# TPSPowerSupply.net
KiCad netlist of a schematic drawn in EAGLE
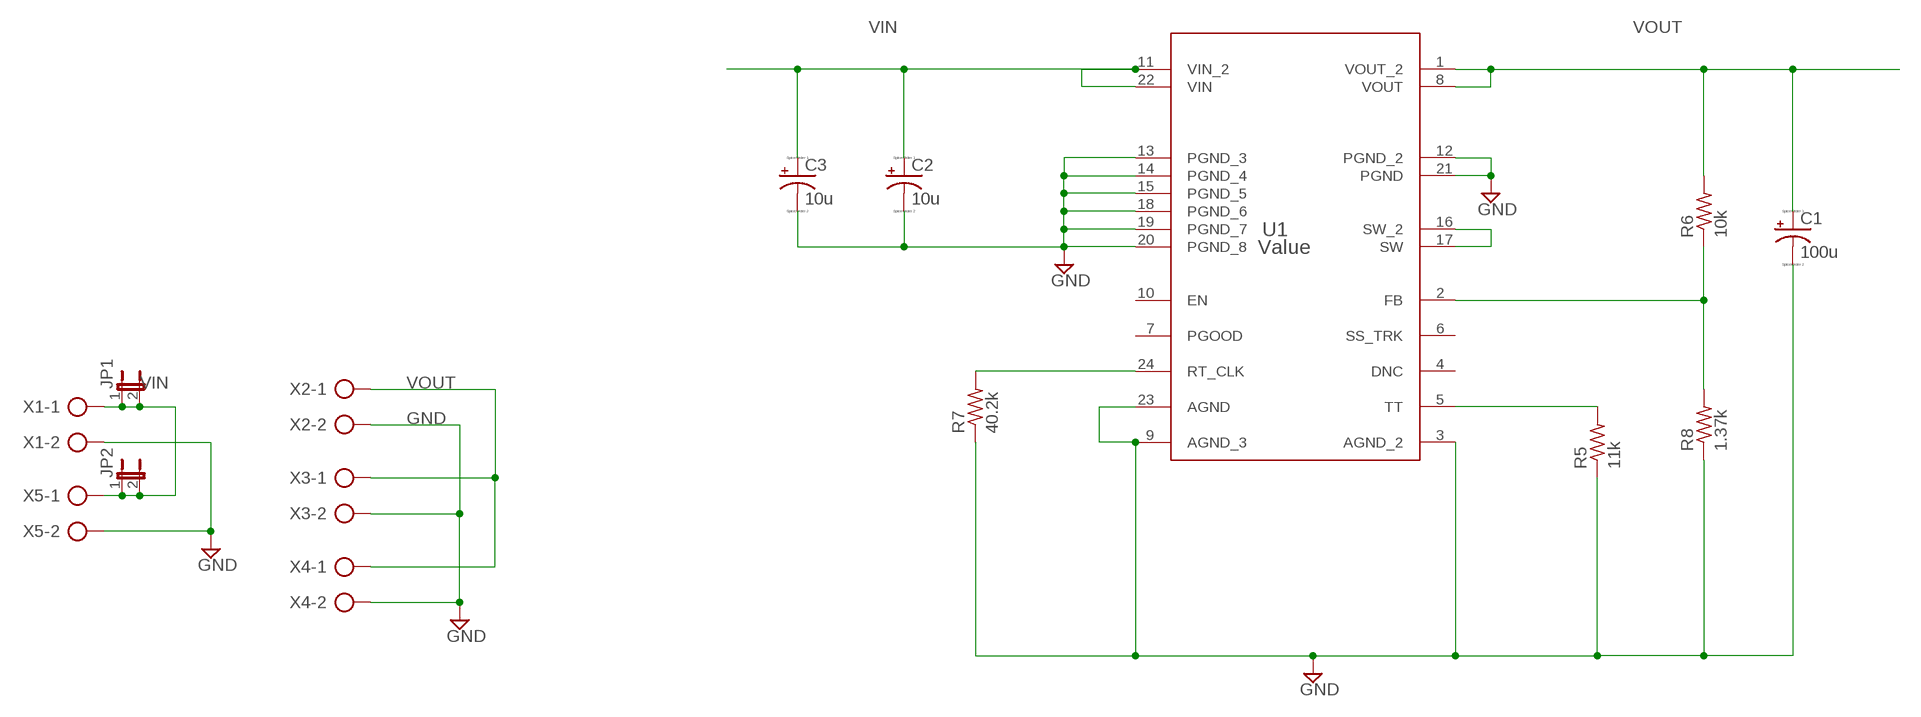
[diagram p0: schematic, sheet 1]

(export (version "E")
  (design (tool "Eeschema 10.0.6"))
  (components
    (comp (ref "C1")
      (value "100u")
      (footprint "eagle-import:TT5D11L")
      (libsource (lib "eagle-import") (part "CPOL-USTT5D11L"))
    )
    (comp (ref "C2")
      (value "10u")
      (footprint "eagle-import:TT5D11L")
      (libsource (lib "eagle-import") (part "CPOL-USTT5D11L"))
    )
    (comp (ref "C3")
      (value "10u")
      (footprint "eagle-import:TT5D11L")
      (libsource (lib "eagle-import") (part "CPOL-USTT5D11L"))
    )
    (comp (ref "JP1")
      (value "JP1E")
      (footprint "eagle-import:JP1")
      (libsource (lib "eagle-import") (part "JP1E"))
    )
    (comp (ref "JP2")
      (value "JP1E")
      (footprint "eagle-import:JP1")
      (libsource (lib "eagle-import") (part "JP1E"))
    )
    (comp (ref "R5")
      (value "11k")
      (footprint "eagle-import:0411_15")
      (libsource (lib "eagle-import") (part "R-US_0411/15"))
    )
    (comp (ref "R6")
      (value "10k")
      (footprint "eagle-import:0411_15")
      (libsource (lib "eagle-import") (part "R-US_0411/15"))
    )
    (comp (ref "R7")
      (value "40.2k")
      (footprint "eagle-import:0411_15")
      (libsource (lib "eagle-import") (part "R-US_0411/15"))
    )
    (comp (ref "R8")
      (value "1.37k")
      (footprint "eagle-import:0411_15")
      (libsource (lib "eagle-import") (part "R-US_0411/15"))
    )
    (comp (ref "U1")
      (value "Value")
      (footprint "eagle-import:MOL0024A")
      (fields
        (field (name "MANUFACTURER") "Texas Instruments")
        (field (name "MANUFACTURER_PART_NUMBER") "TPSM84824MOLR")
      )
      (libsource (lib "eagle-import") (part "TPSM84824MOLR"))
    )
    (comp (ref "X1")
      (value "AK500/2")
      (footprint "eagle-import:AK500_2")
      (libsource (lib "eagle-import") (part "AK500/2"))
    )
    (comp (ref "X2")
      (value "AK500/2")
      (footprint "eagle-import:AK500_2")
      (libsource (lib "eagle-import") (part "AK500/2"))
    )
    (comp (ref "X3")
      (value "AK500/2")
      (footprint "eagle-import:AK500_2")
      (libsource (lib "eagle-import") (part "AK500/2"))
    )
    (comp (ref "X4")
      (value "AK500/2")
      (footprint "eagle-import:AK500_2")
      (libsource (lib "eagle-import") (part "AK500/2"))
    )
    (comp (ref "X5")
      (value "AK500/2")
      (footprint "eagle-import:AK500_2")
      (libsource (lib "eagle-import") (part "AK500/2"))
    )
  )
  (nets
    (net (code "1") (name "/VIN") (class "Default")
      (node (ref "C2") (pin "+") (pinfunction "+_+") (pintype "passive"))
      (node (ref "C3") (pin "+") (pinfunction "+_+") (pintype "passive"))
      (node (ref "JP1") (pin "1") (pinfunction "1_1") (pintype "passive"))
      (node (ref "JP1") (pin "2") (pinfunction "2_2") (pintype "passive"))
      (node (ref "JP2") (pin "1") (pinfunction "1_1") (pintype "passive"))
      (node (ref "JP2") (pin "2") (pinfunction "2_2") (pintype "passive"))
      (node (ref "U1") (pin "11") (pinfunction "VIN_2_11") (pintype "power_in"))
      (node (ref "U1") (pin "22") (pinfunction "VIN_22") (pintype "power_in"))
      (node (ref "X1") (pin "1") (pinfunction "KL_1") (pintype "passive"))
      (node (ref "X5") (pin "1") (pinfunction "KL_1") (pintype "passive"))
    )
    (net (code "2") (name "/VOUT") (class "Default")
      (node (ref "C1") (pin "+") (pinfunction "+_+") (pintype "passive"))
      (node (ref "R6") (pin "2") (pinfunction "2_2") (pintype "passive"))
      (node (ref "U1") (pin "1") (pinfunction "VOUT_2_1") (pintype "power_in"))
      (node (ref "U1") (pin "8") (pinfunction "VOUT_8") (pintype "power_in"))
      (node (ref "X2") (pin "1") (pinfunction "KL_1") (pintype "passive"))
      (node (ref "X3") (pin "1") (pinfunction "KL_1") (pintype "passive"))
      (node (ref "X4") (pin "1") (pinfunction "KL_1") (pintype "passive"))
    )
    (net (code "3") (name "GND") (class "Default")
      (node (ref "C1") (pin "-") (pinfunction "-_-") (pintype "passive"))
      (node (ref "C2") (pin "-") (pinfunction "-_-") (pintype "passive"))
      (node (ref "C3") (pin "-") (pinfunction "-_-") (pintype "passive"))
      (node (ref "R5") (pin "1") (pinfunction "1_1") (pintype "passive"))
      (node (ref "R7") (pin "1") (pinfunction "1_1") (pintype "passive"))
      (node (ref "R8") (pin "1") (pinfunction "1_1") (pintype "passive"))
      (node (ref "U1") (pin "12") (pinfunction "PGND_2_12") (pintype "power_in"))
      (node (ref "U1") (pin "13") (pinfunction "PGND_3_13") (pintype "power_in"))
      (node (ref "U1") (pin "14") (pinfunction "PGND_4_14") (pintype "power_in"))
      (node (ref "U1") (pin "15") (pinfunction "PGND_5_15") (pintype "power_in"))
      (node (ref "U1") (pin "18") (pinfunction "PGND_6_18") (pintype "power_in"))
      (node (ref "U1") (pin "19") (pinfunction "PGND_7_19") (pintype "power_in"))
      (node (ref "U1") (pin "20") (pinfunction "PGND_8_20") (pintype "power_in"))
      (node (ref "U1") (pin "21") (pinfunction "PGND_21") (pintype "power_in"))
      (node (ref "U1") (pin "23") (pinfunction "AGND_23") (pintype "power_in"))
      (node (ref "U1") (pin "3") (pinfunction "AGND_2_3") (pintype "power_in"))
      (node (ref "U1") (pin "9") (pinfunction "AGND_3_9") (pintype "power_in"))
      (node (ref "X1") (pin "2") (pinfunction "KL_2") (pintype "passive"))
      (node (ref "X2") (pin "2") (pinfunction "KL_2") (pintype "passive"))
      (node (ref "X3") (pin "2") (pinfunction "KL_2") (pintype "passive"))
      (node (ref "X4") (pin "2") (pinfunction "KL_2") (pintype "passive"))
      (node (ref "X5") (pin "2") (pinfunction "KL_2") (pintype "passive"))
    )
    (net (code "4") (name "Net-(U1-FB)") (class "Default")
      (node (ref "R6") (pin "1") (pinfunction "1_1") (pintype "passive"))
      (node (ref "R8") (pin "2") (pinfunction "2_2") (pintype "passive"))
      (node (ref "U1") (pin "2") (pinfunction "FB_2") (pintype "input"))
    )
    (net (code "5") (name "Net-(U1-RT_CLK)") (class "Default")
      (node (ref "R7") (pin "2") (pinfunction "2_2") (pintype "passive"))
      (node (ref "U1") (pin "24") (pinfunction "RT_CLK_24") (pintype "input"))
    )
    (net (code "6") (name "Net-(U1-SW)") (class "Default")
      (node (ref "U1") (pin "16") (pinfunction "SW_2_16") (pintype "output"))
      (node (ref "U1") (pin "17") (pinfunction "SW_17") (pintype "output"))
    )
    (net (code "7") (name "Net-(U1-TT)") (class "Default")
      (node (ref "R5") (pin "2") (pinfunction "2_2") (pintype "passive"))
      (node (ref "U1") (pin "5") (pinfunction "TT_5") (pintype "passive"))
    )
    (net (code "8") (name "unconnected-(U1-DNC-Pad4)") (class "Default")
      (node (ref "U1") (pin "4") (pinfunction "DNC_4") (pintype "passive"))
    )
    (net (code "9") (name "unconnected-(U1-EN-Pad10)") (class "Default")
      (node (ref "U1") (pin "10") (pinfunction "EN_10") (pintype "input"))
    )
    (net (code "10") (name "unconnected-(U1-PGOOD-Pad7)") (class "Default")
      (node (ref "U1") (pin "7") (pinfunction "PGOOD_7") (pintype "passive"))
    )
    (net (code "11") (name "unconnected-(U1-SS_TRK-Pad6)") (class "Default")
      (node (ref "U1") (pin "6") (pinfunction "SS_TRK_6") (pintype "passive"))
    )
  )
)
